# MCU.net
KiCad netlist of a schematic drawn in Altium Designer
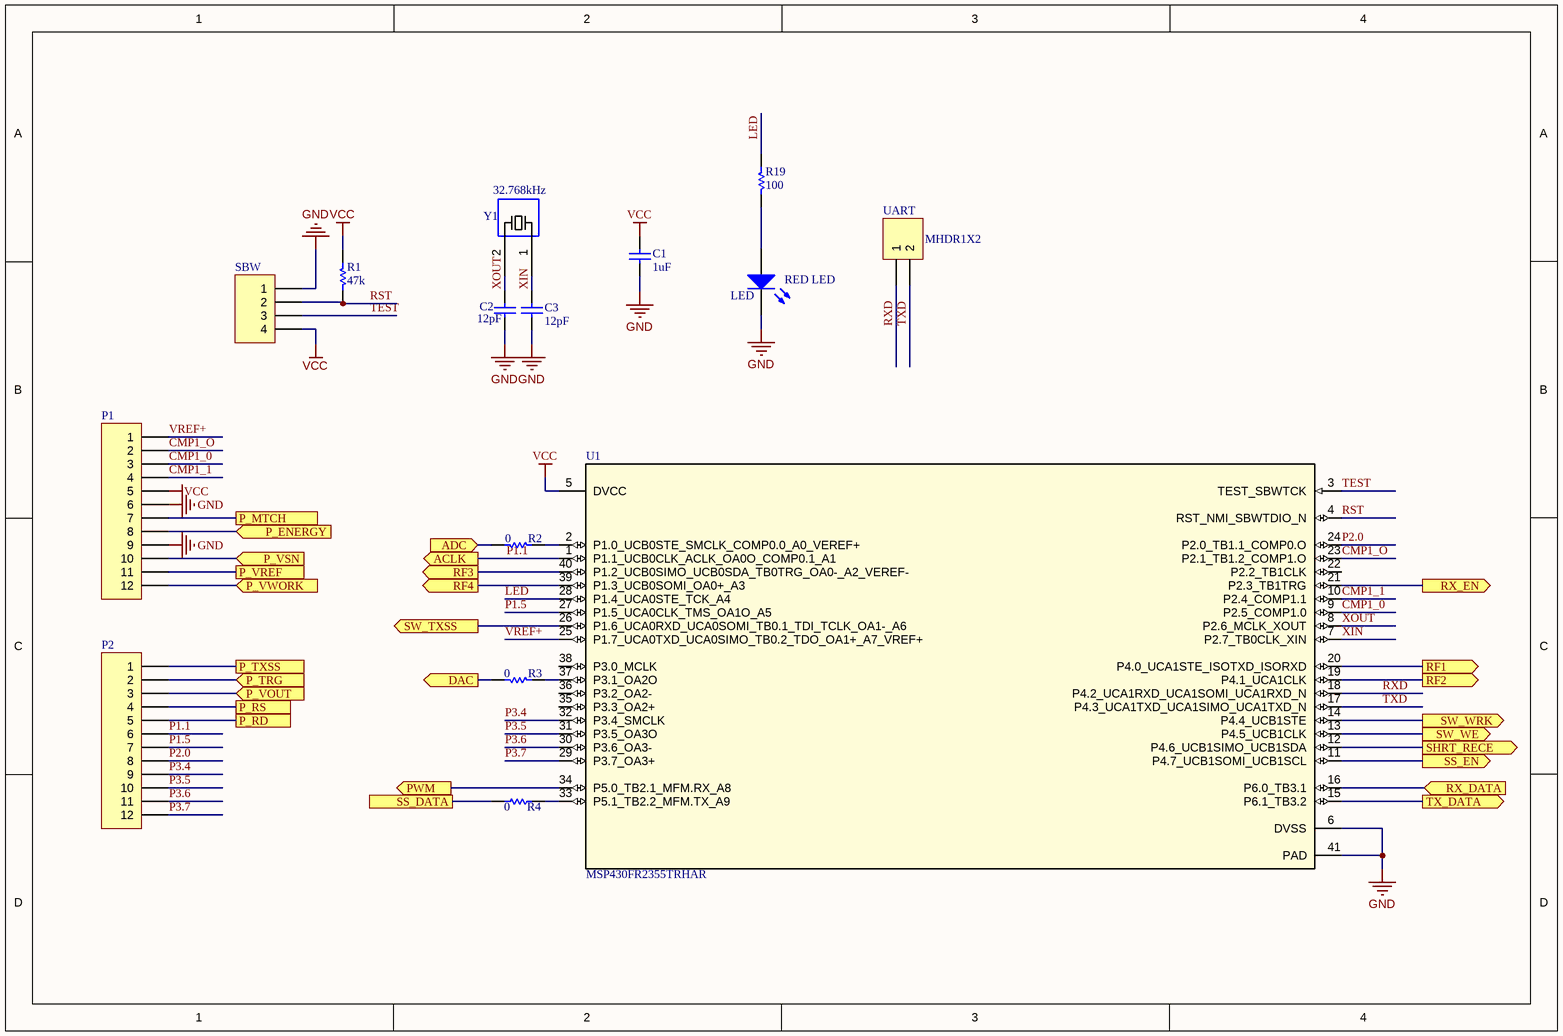
[diagram p0: MCU.SchDoc]

(export (version "E")
  (design (tool "Eeschema 10.0.6"))
  (components
    (comp (ref "C1")
      (value "1uF")
      (footprint "0402")
      (description "Ceramic Capacitor (Surface Mount)")
      (fields (field (name "MANUFACTURER") "Generic Ceramic Chip Cap (TBD)"))
      (libsource (lib "Sensor") (part "Cap"))
    )
    (comp (ref "C2")
      (value "12pF")
      (footprint "0402")
      (description "Ceramic Capacitor (Surface Mount)")
      (fields (field (name "MANUFACTURER") "Generic Ceramic Chip Cap (TBD)"))
      (libsource (lib "Sensor") (part "Cap"))
    )
    (comp (ref "C3")
      (value "12pF")
      (footprint "0402")
      (description "Ceramic Capacitor (Surface Mount)")
      (fields (field (name "MANUFACTURER") "Generic Ceramic Chip Cap (TBD)"))
      (libsource (lib "Sensor") (part "Cap"))
    )
    (comp (ref "LED")
      (value "RED LED")
      (footprint "Diode - 0603")
      (description "Typical RED, GREEN, YELLOW, AMBER GaAs LED")
      (libsource (lib "Sensor") (part "Diode - LED"))
    )
    (comp (ref "P1")
      (value "~")
      (footprint "MHDR1X12")
      (description "Header, 12-Pin")
      (fields (field (name "PUBLISHER") "Altium Limited"))
      (libsource (lib "Miscellaneous Connectors") (part "MHDR1X12"))
    )
    (comp (ref "P2")
      (value "~")
      (footprint "MHDR1X12")
      (description "Header, 12-Pin")
      (fields (field (name "PUBLISHER") "Altium Limited"))
      (libsource (lib "Miscellaneous Connectors") (part "MHDR1X12"))
    )
    (comp (ref "R1")
      (value "47k")
      (footprint "0402")
      (description "Chip Resistor (Surface Mount)")
      (fields
        (field (name "MANUFACTURER") "Panasonic")
        (field (name "MANUFACTURER PART NUMBER") "ERJ-2RKF4702X")
      )
      (libsource (lib "Sensor") (part "Res"))
    )
    (comp (ref "R2")
      (value "0")
      (footprint "0402")
      (description "Chip Resistor (Surface Mount)")
      (fields
        (field (name "MANUFACTURER") "Panasonic")
        (field (name "MANUFACTURER PART NUMBER") "ERJ-2RKF4702X")
      )
      (libsource (lib "Sensor") (part "Res"))
    )
    (comp (ref "R3")
      (value "0")
      (footprint "0402")
      (description "Chip Resistor (Surface Mount)")
      (fields
        (field (name "MANUFACTURER") "Panasonic")
        (field (name "MANUFACTURER PART NUMBER") "ERJ-2RKF4702X")
      )
      (libsource (lib "Sensor") (part "Res"))
    )
    (comp (ref "R4")
      (value "0")
      (footprint "0402")
      (description "Chip Resistor (Surface Mount)")
      (fields
        (field (name "MANUFACTURER") "Panasonic")
        (field (name "MANUFACTURER PART NUMBER") "ERJ-2RKF4702X")
      )
      (libsource (lib "Sensor") (part "Res"))
    )
    (comp (ref "R19")
      (value "100")
      (footprint "0402")
      (description "Chip Resistor (Surface Mount)")
      (fields
        (field (name "MANUFACTURER") "Panasonic")
        (field (name "MANUFACTURER PART NUMBER") "ERJ-2RKF4702X")
      )
      (libsource (lib "Sensor") (part "Res"))
    )
    (comp (ref "SBW")
      (value "~")
      (footprint "MHDR1X4")
      (description "Header, 4-Pin")
      (fields
        (field (name "MANUFACTURER PART NUMBER") "851-43-004-20-001000")
        (field (name "DIGI-KEY PART NUMBER") "ED90474-ND")
      )
      (libsource (lib "Miscellaneous Connectors") (part "MHDR1X4"))
    )
    (comp (ref "U1")
      (value "MSP430FR2355TRHAR")
      (footprint "MSP430FR2355TRHA_RHA0040E")
      (description "24MHz 105C integrated analog microcontroller with 32KB FRAM, Op-Amps/PGAs, 12-bit DACs, 12-bit ADC")
      (fields (field (name "COPYRIGHT") "Copyright (C) 2022 Ultra Librarian. All rights reserved."))
      (libsource (lib "Sensor") (part "MSP430FR2355TRHAR"))
    )
    (comp (ref "UART")
      (value "MHDR1X2")
      (footprint "MHDR1X2")
      (description "Header, 2-Pin")
      (fields (field (name "PUBLISHER") "Altium Limited"))
      (libsource (lib "Miscellaneous Connectors") (part "MHDR1X2"))
    )
    (comp (ref "Y1")
      (value "32.768kHz")
      (footprint "XTAL [3.20mm x 1.50mm]")
      (description "Crystal Oscillator - [3.20mm x 1.50mm]")
      (fields
        (field (name "DIGI-KEY PART NUMBER") "example: SE2413CT-ND")
        (field (name "MANUFACTURER") "Epson Toyocom Corporation")
      )
      (libsource (lib "Sensor") (part "XTAL 2-pins"))
    )
  )
  (nets
    (net (code "1") (name "/ADC") (class "Default")
      (node (ref "R2") (pin "2") (pinfunction "2_2") (pintype "passive"))
    )
    (net (code "2") (name "/CMP1_0") (class "Default")
      (node (ref "P1") (pin "3") (pinfunction "3_3") (pintype "passive"))
      (node (ref "U1") (pin "9") (pinfunction "P2.5_COMP1.0_9") (pintype "bidirectional"))
    )
    (net (code "3") (name "/CMP1_1") (class "Default")
      (node (ref "P1") (pin "4") (pinfunction "4_4") (pintype "passive"))
      (node (ref "U1") (pin "10") (pinfunction "P2.4_COMP1.1_10") (pintype "bidirectional"))
    )
    (net (code "4") (name "/CMP1_O") (class "Default")
      (node (ref "P1") (pin "2") (pinfunction "2_2") (pintype "passive"))
      (node (ref "U1") (pin "23") (pinfunction "P2.1_TB1.2_COMP1.O_23") (pintype "bidirectional"))
    )
    (net (code "5") (name "/DAC") (class "Default")
      (node (ref "R3") (pin "2") (pinfunction "2_2") (pintype "passive"))
    )
    (net (code "6") (name "/LED") (class "Default")
      (node (ref "R19") (pin "2") (pinfunction "2_2") (pintype "passive"))
      (node (ref "U1") (pin "28") (pinfunction "P1.4_UCA0STE_TCK_A4_28") (pintype "bidirectional"))
    )
    (net (code "7") (name "/P1.1") (class "Default")
      (node (ref "P2") (pin "6") (pinfunction "6_6") (pintype "passive"))
      (node (ref "U1") (pin "1") (pinfunction "P1.1_UCB0CLK_ACLK_OA0O_COMP0.1_A1_1") (pintype "bidirectional"))
    )
    (net (code "8") (name "/P1.5") (class "Default")
      (node (ref "P2") (pin "7") (pinfunction "7_7") (pintype "passive"))
      (node (ref "U1") (pin "27") (pinfunction "P1.5_UCA0CLK_TMS_OA1O_A5_27") (pintype "bidirectional"))
    )
    (net (code "9") (name "/P2.0") (class "Default")
      (node (ref "P2") (pin "8") (pinfunction "8_8") (pintype "passive"))
      (node (ref "U1") (pin "24") (pinfunction "P2.0_TB1.1_COMP0.O_24") (pintype "bidirectional"))
    )
    (net (code "10") (name "/P3.4") (class "Default")
      (node (ref "P2") (pin "9") (pinfunction "9_9") (pintype "passive"))
      (node (ref "U1") (pin "32") (pinfunction "P3.4_SMCLK_32") (pintype "bidirectional"))
    )
    (net (code "11") (name "/P3.5") (class "Default")
      (node (ref "P2") (pin "10") (pinfunction "10_10") (pintype "passive"))
      (node (ref "U1") (pin "31") (pinfunction "P3.5_OA3O_31") (pintype "bidirectional"))
    )
    (net (code "12") (name "/P3.6") (class "Default")
      (node (ref "P2") (pin "11") (pinfunction "11_11") (pintype "passive"))
      (node (ref "U1") (pin "30") (pinfunction "P3.6_OA3-_30") (pintype "bidirectional"))
    )
    (net (code "13") (name "/P3.7") (class "Default")
      (node (ref "P2") (pin "12") (pinfunction "12_12") (pintype "passive"))
      (node (ref "U1") (pin "29") (pinfunction "P3.7_OA3+_29") (pintype "bidirectional"))
    )
    (net (code "14") (name "/PWM") (class "Default")
      (node (ref "U1") (pin "34") (pinfunction "P5.0_TB2.1_MFM.RX_A8_34") (pintype "bidirectional"))
    )
    (net (code "15") (name "/P_ENERGY") (class "Default")
      (node (ref "P1") (pin "8") (pinfunction "8_8") (pintype "passive"))
    )
    (net (code "16") (name "/P_MTCH") (class "Default")
      (node (ref "P1") (pin "7") (pinfunction "7_7") (pintype "passive"))
    )
    (net (code "17") (name "/P_RD") (class "Default")
      (node (ref "P2") (pin "5") (pinfunction "5_5") (pintype "passive"))
    )
    (net (code "18") (name "/P_RS") (class "Default")
      (node (ref "P2") (pin "4") (pinfunction "4_4") (pintype "passive"))
    )
    (net (code "19") (name "/P_TRG") (class "Default")
      (node (ref "P2") (pin "2") (pinfunction "2_2") (pintype "passive"))
    )
    (net (code "20") (name "/P_TXSS") (class "Default")
      (node (ref "P2") (pin "1") (pinfunction "1_1") (pintype "passive"))
    )
    (net (code "21") (name "/P_VOUT") (class "Default")
      (node (ref "P2") (pin "3") (pinfunction "3_3") (pintype "passive"))
    )
    (net (code "22") (name "/P_VREF") (class "Default")
      (node (ref "P1") (pin "11") (pinfunction "11_11") (pintype "passive"))
    )
    (net (code "23") (name "/P_VSN") (class "Default")
      (node (ref "P1") (pin "10") (pinfunction "10_10") (pintype "passive"))
    )
    (net (code "24") (name "/P_VWORK") (class "Default")
      (node (ref "P1") (pin "12") (pinfunction "12_12") (pintype "passive"))
    )
    (net (code "25") (name "/RF1") (class "Default")
      (node (ref "U1") (pin "20") (pinfunction "P4.0_UCA1STE_ISOTXD_ISORXD_20") (pintype "bidirectional"))
    )
    (net (code "26") (name "/RF2") (class "Default")
      (node (ref "U1") (pin "19") (pinfunction "P4.1_UCA1CLK_19") (pintype "bidirectional"))
    )
    (net (code "27") (name "/RF3") (class "Default")
      (node (ref "U1") (pin "40") (pinfunction "P1.2_UCB0SIMO_UCB0SDA_TB0TRG_OA0-_A2_VEREF-_40") (pintype "bidirectional"))
    )
    (net (code "28") (name "/RF4") (class "Default")
      (node (ref "U1") (pin "39") (pinfunction "P1.3_UCB0SOMI_OA0+_A3_39") (pintype "bidirectional"))
    )
    (net (code "29") (name "/RST") (class "Default")
      (node (ref "R1") (pin "1") (pinfunction "1_1") (pintype "passive"))
      (node (ref "SBW") (pin "2") (pinfunction "2_2") (pintype "passive"))
      (node (ref "U1") (pin "4") (pinfunction "RST_NMI_SBWTDIO_N_4") (pintype "bidirectional"))
    )
    (net (code "30") (name "/RXD") (class "Default")
      (node (ref "U1") (pin "18") (pinfunction "P4.2_UCA1RXD_UCA1SOMI_UCA1RXD_N_18") (pintype "bidirectional"))
      (node (ref "UART") (pin "1") (pinfunction "1_1") (pintype "passive"))
    )
    (net (code "31") (name "/RX_DATA") (class "Default")
      (node (ref "U1") (pin "16") (pinfunction "P6.0_TB3.1_16") (pintype "bidirectional"))
    )
    (net (code "32") (name "/RX_EN") (class "Default")
      (node (ref "U1") (pin "21") (pinfunction "P2.3_TB1TRG_21") (pintype "bidirectional"))
    )
    (net (code "33") (name "/SHRT_RECE") (class "Default")
      (node (ref "U1") (pin "12") (pinfunction "P4.6_UCB1SIMO_UCB1SDA_12") (pintype "bidirectional"))
    )
    (net (code "34") (name "/SS_DATA") (class "Default")
      (node (ref "R4") (pin "1") (pinfunction "1_1") (pintype "passive"))
    )
    (net (code "35") (name "/SS_EN") (class "Default")
      (node (ref "U1") (pin "11") (pinfunction "P4.7_UCB1SOMI_UCB1SCL_11") (pintype "bidirectional"))
    )
    (net (code "36") (name "/SW_TXSS") (class "Default")
      (node (ref "U1") (pin "26") (pinfunction "P1.6_UCA0RXD_UCA0SOMI_TB0.1_TDI_TCLK_OA1-_A6_26") (pintype "bidirectional"))
    )
    (net (code "37") (name "/SW_WE") (class "Default")
      (node (ref "U1") (pin "13") (pinfunction "P4.5_UCB1CLK_13") (pintype "bidirectional"))
    )
    (net (code "38") (name "/SW_WRK") (class "Default")
      (node (ref "U1") (pin "14") (pinfunction "P4.4_UCB1STE_14") (pintype "bidirectional"))
    )
    (net (code "39") (name "/TEST") (class "Default")
      (node (ref "SBW") (pin "3") (pinfunction "3_3") (pintype "passive"))
      (node (ref "U1") (pin "3") (pinfunction "TEST_SBWTCK_3") (pintype "input"))
    )
    (net (code "40") (name "/TXD") (class "Default")
      (node (ref "U1") (pin "17") (pinfunction "P4.3_UCA1TXD_UCA1SIMO_UCA1TXD_N_17") (pintype "bidirectional"))
      (node (ref "UART") (pin "2") (pinfunction "2_2") (pintype "passive"))
    )
    (net (code "41") (name "/TX_DATA") (class "Default")
      (node (ref "U1") (pin "15") (pinfunction "P6.1_TB3.2_15") (pintype "bidirectional"))
    )
    (net (code "42") (name "/VREF+") (class "Default")
      (node (ref "P1") (pin "1") (pinfunction "1_1") (pintype "passive"))
      (node (ref "U1") (pin "25") (pinfunction "P1.7_UCA0TXD_UCA0SIMO_TB0.2_TDO_OA1+_A7_VREF+_25") (pintype "bidirectional"))
    )
    (net (code "43") (name "/XIN") (class "Default")
      (node (ref "C3") (pin "1") (pinfunction "1_1") (pintype "passive"))
      (node (ref "U1") (pin "7") (pinfunction "P2.7_TB0CLK_XIN_7") (pintype "bidirectional"))
      (node (ref "Y1") (pin "1") (pinfunction "1_1") (pintype "power_in"))
    )
    (net (code "44") (name "/XOUT") (class "Default")
      (node (ref "C2") (pin "1") (pinfunction "1_1") (pintype "passive"))
      (node (ref "U1") (pin "8") (pinfunction "P2.6_MCLK_XOUT_8") (pintype "bidirectional"))
      (node (ref "Y1") (pin "2") (pinfunction "2_2") (pintype "power_in"))
    )
    (net (code "45") (name "GND") (class "Default")
      (node (ref "C1") (pin "2") (pinfunction "2_2") (pintype "passive"))
      (node (ref "C2") (pin "2") (pinfunction "2_2") (pintype "passive"))
      (node (ref "C3") (pin "2") (pinfunction "2_2") (pintype "passive"))
      (node (ref "LED") (pin "2") (pinfunction "K_2") (pintype "passive"))
      (node (ref "P1") (pin "6") (pinfunction "6_6") (pintype "passive"))
      (node (ref "P1") (pin "9") (pinfunction "9_9") (pintype "passive"))
      (node (ref "SBW") (pin "1") (pinfunction "1_1") (pintype "passive"))
      (node (ref "U1") (pin "41") (pinfunction "PAD_41") (pintype "passive"))
      (node (ref "U1") (pin "6") (pinfunction "DVSS_6") (pintype "power_in"))
    )
    (net (code "46") (name "Net-(LED-A)") (class "Default")
      (node (ref "LED") (pin "1") (pinfunction "A_1") (pintype "passive"))
      (node (ref "R19") (pin "1") (pinfunction "1_1") (pintype "passive"))
    )
    (net (code "47") (name "Net-(U1-P1.0_UCB0STE_SMCLK_COMP0.0_A0_VEREF+)") (class "Default")
      (node (ref "R2") (pin "1") (pinfunction "1_1") (pintype "passive"))
      (node (ref "U1") (pin "2") (pinfunction "P1.0_UCB0STE_SMCLK_COMP0.0_A0_VEREF+_2") (pintype "bidirectional"))
    )
    (net (code "48") (name "Net-(U1-P3.1_OA2O)") (class "Default")
      (node (ref "R3") (pin "1") (pinfunction "1_1") (pintype "passive"))
      (node (ref "U1") (pin "37") (pinfunction "P3.1_OA2O_37") (pintype "bidirectional"))
    )
    (net (code "49") (name "Net-(U1-P5.1_TB2.2_MFM.TX_A9)") (class "Default")
      (node (ref "R4") (pin "2") (pinfunction "2_2") (pintype "passive"))
      (node (ref "U1") (pin "33") (pinfunction "P5.1_TB2.2_MFM.TX_A9_33") (pintype "bidirectional"))
    )
    (net (code "50") (name "VCC") (class "Default")
      (node (ref "C1") (pin "1") (pinfunction "1_1") (pintype "passive"))
      (node (ref "P1") (pin "5") (pinfunction "5_5") (pintype "passive"))
      (node (ref "R1") (pin "2") (pinfunction "2_2") (pintype "passive"))
      (node (ref "SBW") (pin "4") (pinfunction "4_4") (pintype "passive"))
      (node (ref "U1") (pin "5") (pinfunction "DVCC_5") (pintype "power_in"))
    )
    (net (code "51") (name "unconnected-(U1-P2.2_TB1CLK-Pad22)") (class "Default")
      (node (ref "U1") (pin "22") (pinfunction "P2.2_TB1CLK_22") (pintype "bidirectional"))
    )
    (net (code "52") (name "unconnected-(U1-P3.0_MCLK-Pad38)") (class "Default")
      (node (ref "U1") (pin "38") (pinfunction "P3.0_MCLK_38") (pintype "bidirectional"))
    )
    (net (code "53") (name "unconnected-(U1-P3.2_OA2--Pad36)") (class "Default")
      (node (ref "U1") (pin "36") (pinfunction "P3.2_OA2-_36") (pintype "bidirectional"))
    )
    (net (code "54") (name "unconnected-(U1-P3.3_OA2+-Pad35)") (class "Default")
      (node (ref "U1") (pin "35") (pinfunction "P3.3_OA2+_35") (pintype "bidirectional"))
    )
  )
)
